# 9key_rev0_1a.net
KiCad netlist of a schematic drawn in EAGLE
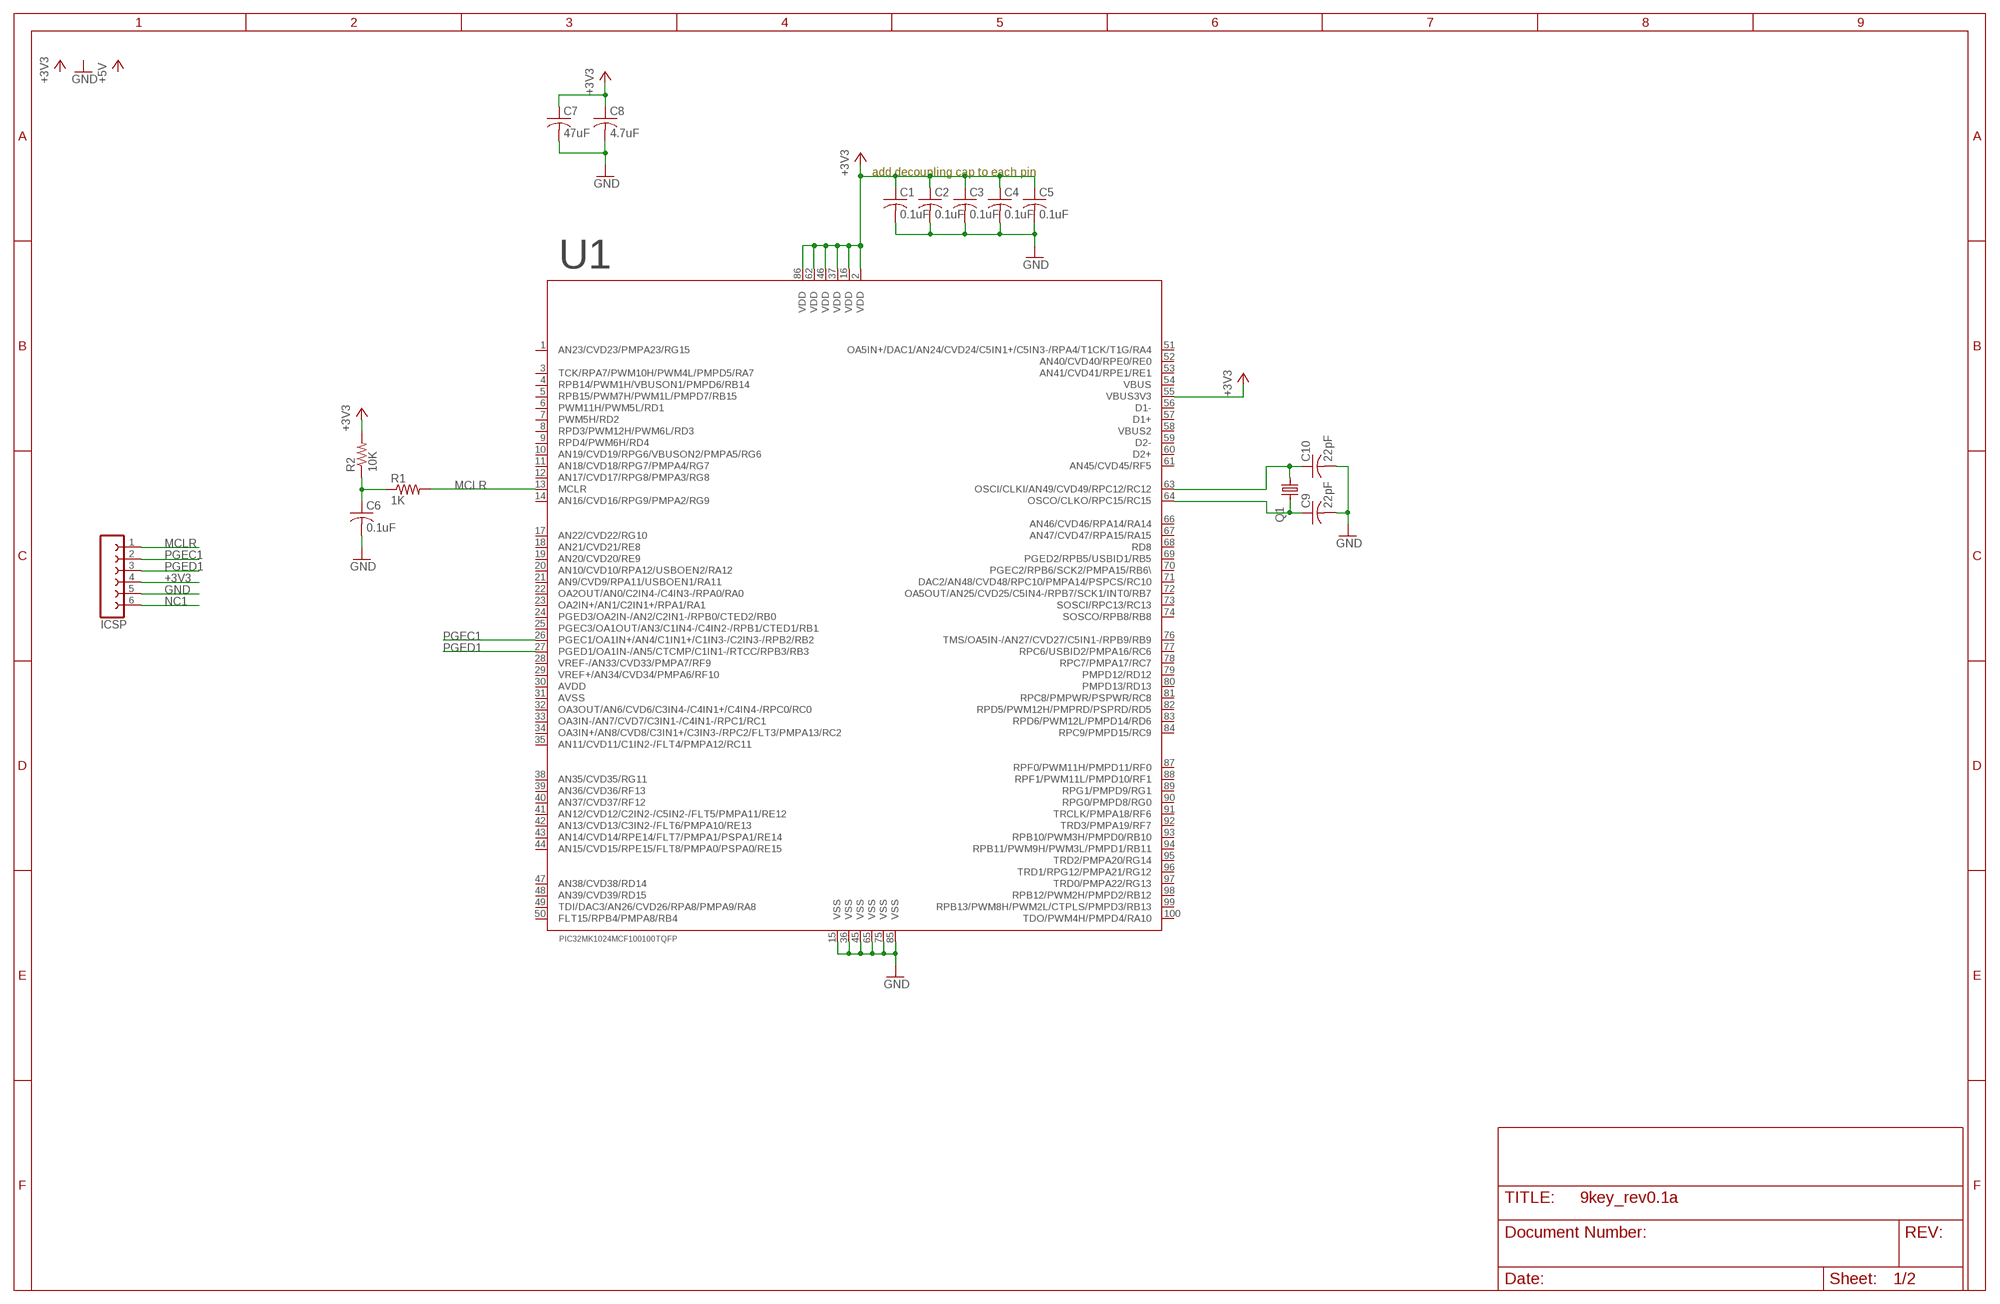
[diagram p0: schematic, sheet 1]
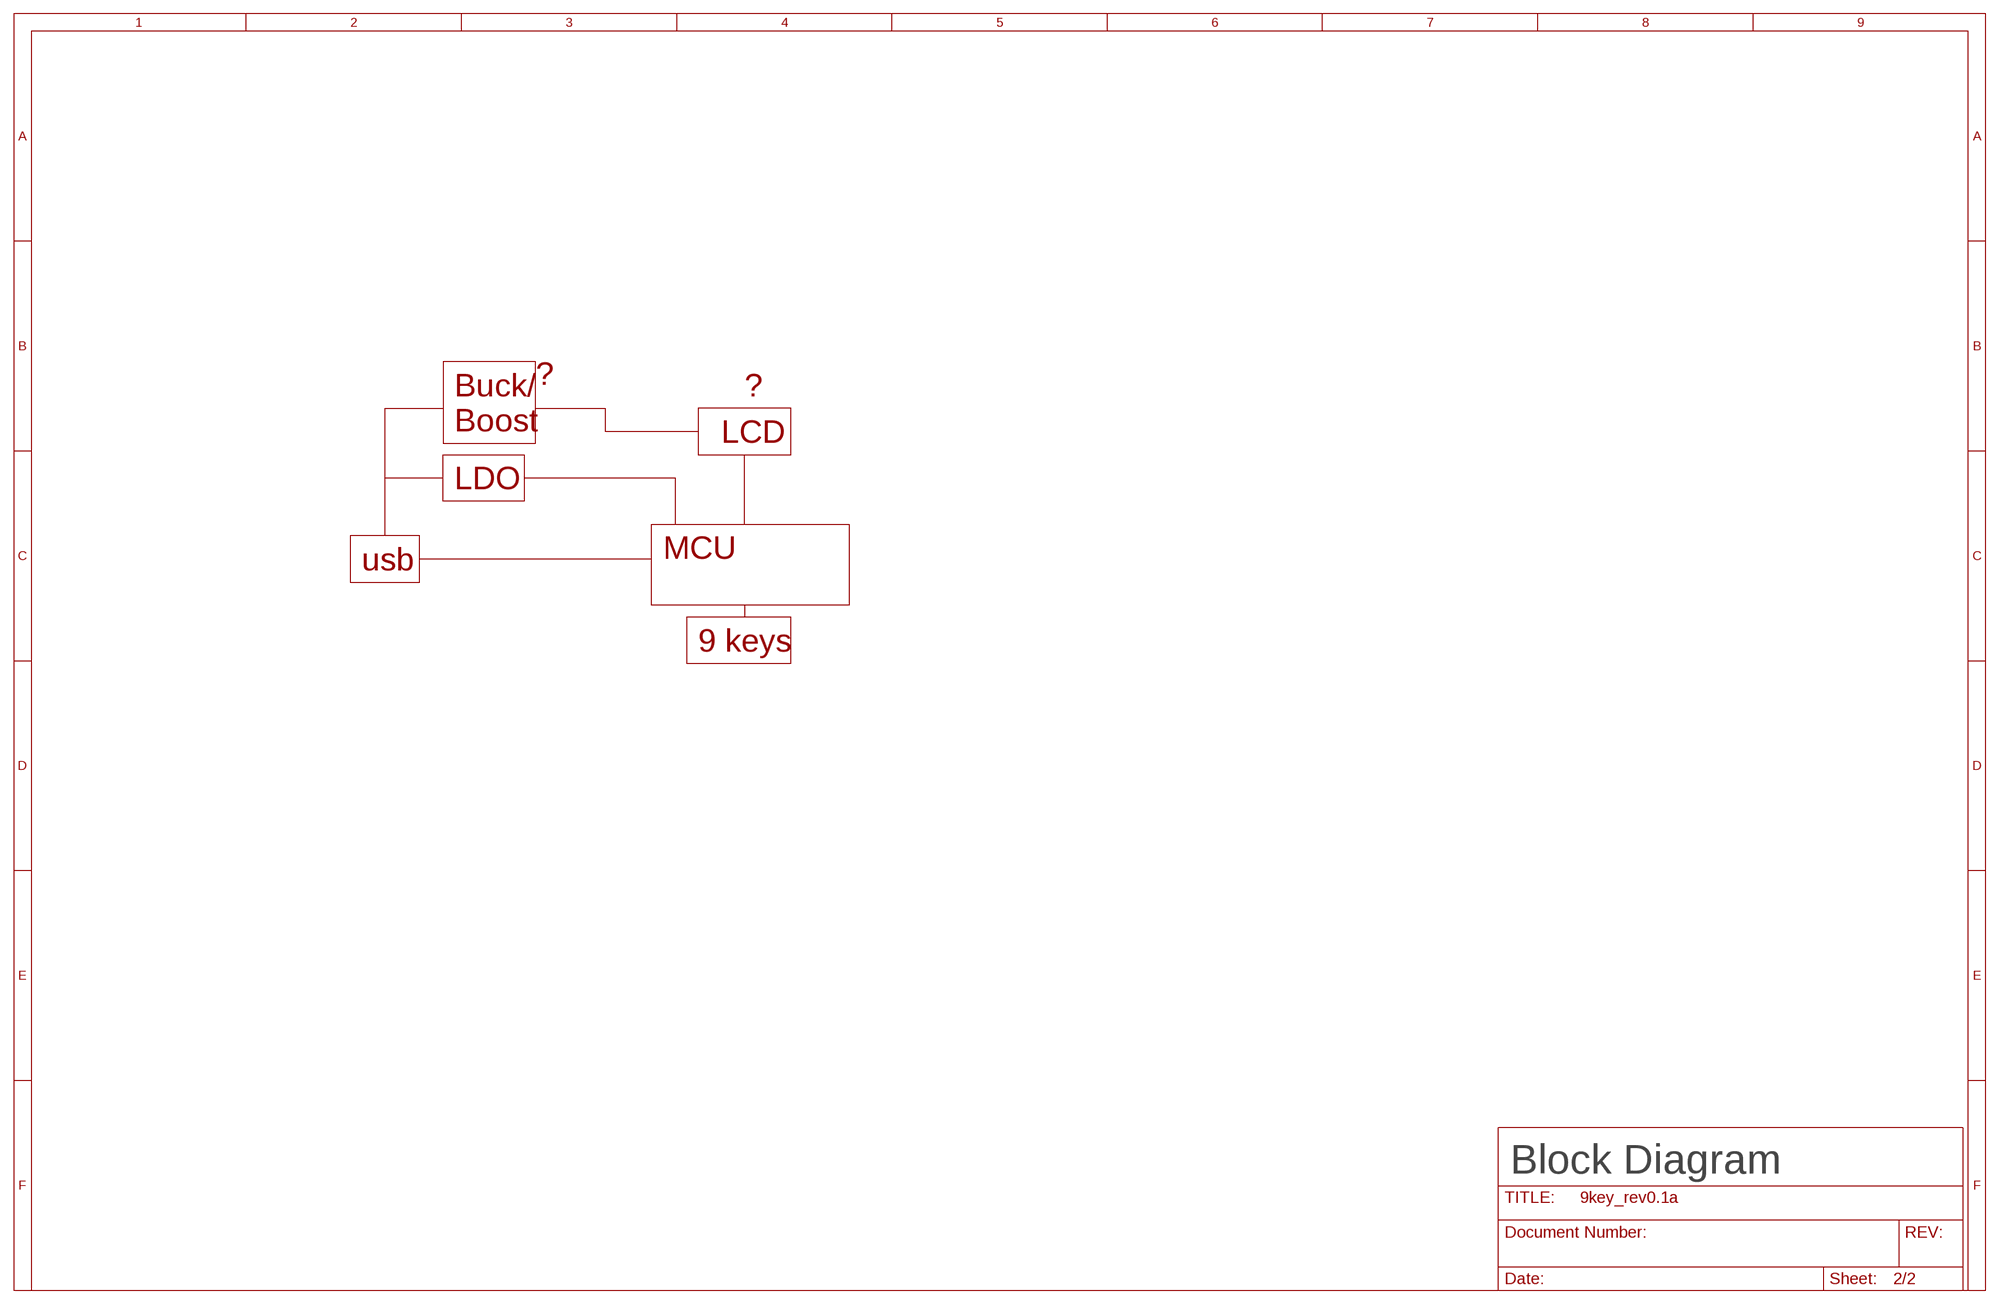
[diagram p1: schematic, sheet 2]

(export (version "E")
  (design (tool "Eeschema 10.0.6"))
  (components
    (comp (ref "C1")
      (value "0.1uF")
      (footprint "eagle-import:C0805")
      (libsource (lib "eagle-import") (part "C-USC0805"))
    )
    (comp (ref "C2")
      (value "0.1uF")
      (footprint "eagle-import:C0805")
      (libsource (lib "eagle-import") (part "C-USC0805"))
    )
    (comp (ref "C3")
      (value "0.1uF")
      (footprint "eagle-import:C0805")
      (libsource (lib "eagle-import") (part "C-USC0805"))
    )
    (comp (ref "C4")
      (value "0.1uF")
      (footprint "eagle-import:C0805")
      (libsource (lib "eagle-import") (part "C-USC0805"))
    )
    (comp (ref "C5")
      (value "0.1uF")
      (footprint "eagle-import:C0805")
      (libsource (lib "eagle-import") (part "C-USC0805"))
    )
    (comp (ref "C6")
      (value "0.1uF")
      (footprint "eagle-import:C0805")
      (libsource (lib "eagle-import") (part "C-USC0805"))
    )
    (comp (ref "C7")
      (value "47uF")
      (footprint "eagle-import:C0805")
      (libsource (lib "eagle-import") (part "C-USC0805"))
    )
    (comp (ref "C8")
      (value "4.7uF")
      (footprint "eagle-import:C0805")
      (libsource (lib "eagle-import") (part "C-USC0805"))
    )
    (comp (ref "C9")
      (value "22pF")
      (footprint "eagle-import:C0603")
      (libsource (lib "eagle-import") (part "C-USC0603"))
    )
    (comp (ref "C10")
      (value "22pF")
      (footprint "eagle-import:C0603")
      (libsource (lib "eagle-import") (part "C-USC0603"))
    )
    (comp (ref "ICSP")
      (value "FE06-1")
      (footprint "eagle-import:FE06")
      (libsource (lib "eagle-import") (part "FE06-1"))
    )
    (comp (ref "Q1")
      (value "KX-7")
      (footprint "eagle-import:3.2X2.5_KX-7")
      (libsource (lib "eagle-import") (part "KX-7"))
    )
    (comp (ref "R1")
      (value "1K")
      (footprint "eagle-import:R0805")
      (libsource (lib "eagle-import") (part "R-US_R0805"))
    )
    (comp (ref "R2")
      (value "10K")
      (footprint "eagle-import:R0805")
      (libsource (lib "eagle-import") (part "R-US_R0805"))
    )
    (comp (ref "U1")
      (value "PIC32MK1024MCF100100TQFP")
      (footprint "eagle-import:PIC32MK1024MCF100")
      (libsource (lib "eagle-import") (part "PIC32MK1024MCF100100TQFP"))
    )
  )
  (nets
    (net (code "1") (name "+3V3") (class "Default")
      (node (ref "C1") (pin "1") (pinfunction "1_1") (pintype "passive"))
      (node (ref "C2") (pin "1") (pinfunction "1_1") (pintype "passive"))
      (node (ref "C3") (pin "1") (pinfunction "1_1") (pintype "passive"))
      (node (ref "C4") (pin "1") (pinfunction "1_1") (pintype "passive"))
      (node (ref "C5") (pin "1") (pinfunction "1_1") (pintype "passive"))
      (node (ref "C7") (pin "1") (pinfunction "1_1") (pintype "passive"))
      (node (ref "C8") (pin "1") (pinfunction "1_1") (pintype "passive"))
      (node (ref "ICSP") (pin "4") (pinfunction "4_4") (pintype "passive"))
      (node (ref "R2") (pin "2") (pinfunction "2_2") (pintype "passive"))
      (node (ref "U1") (pin "16") (pinfunction "VDD_16") (pintype "bidirectional"))
      (node (ref "U1") (pin "2") (pinfunction "VDD_2") (pintype "bidirectional"))
      (node (ref "U1") (pin "37") (pinfunction "VDD_37") (pintype "bidirectional"))
      (node (ref "U1") (pin "46") (pinfunction "VDD_46") (pintype "bidirectional"))
      (node (ref "U1") (pin "55") (pinfunction "VBUS3V3_55") (pintype "bidirectional"))
      (node (ref "U1") (pin "62") (pinfunction "VDD_62") (pintype "bidirectional"))
      (node (ref "U1") (pin "86") (pinfunction "VDD_86") (pintype "bidirectional"))
    )
    (net (code "3") (name "GND") (class "Default")
      (node (ref "C1") (pin "2") (pinfunction "2_2") (pintype "passive"))
      (node (ref "C10") (pin "2") (pinfunction "2_2") (pintype "passive"))
      (node (ref "C2") (pin "2") (pinfunction "2_2") (pintype "passive"))
      (node (ref "C3") (pin "2") (pinfunction "2_2") (pintype "passive"))
      (node (ref "C4") (pin "2") (pinfunction "2_2") (pintype "passive"))
      (node (ref "C5") (pin "2") (pinfunction "2_2") (pintype "passive"))
      (node (ref "C6") (pin "2") (pinfunction "2_2") (pintype "passive"))
      (node (ref "C7") (pin "2") (pinfunction "2_2") (pintype "passive"))
      (node (ref "C8") (pin "2") (pinfunction "2_2") (pintype "passive"))
      (node (ref "C9") (pin "2") (pinfunction "2_2") (pintype "passive"))
      (node (ref "ICSP") (pin "5") (pinfunction "5_5") (pintype "passive"))
      (node (ref "U1") (pin "15") (pinfunction "VSS_15") (pintype "bidirectional"))
      (node (ref "U1") (pin "36") (pinfunction "VSS_36") (pintype "bidirectional"))
      (node (ref "U1") (pin "45") (pinfunction "VSS_45") (pintype "bidirectional"))
      (node (ref "U1") (pin "65") (pinfunction "VSS_65") (pintype "bidirectional"))
      (node (ref "U1") (pin "75") (pinfunction "VSS_75") (pintype "bidirectional"))
      (node (ref "U1") (pin "85") (pinfunction "VSS_85") (pintype "bidirectional"))
    )
    (net (code "4") (name "MCLR") (class "Default")
      (node (ref "ICSP") (pin "1") (pinfunction "1_1") (pintype "passive"))
      (node (ref "R1") (pin "2") (pinfunction "2_2") (pintype "passive"))
      (node (ref "U1") (pin "13") (pinfunction "MCLR_13") (pintype "bidirectional"))
    )
    (net (code "5") (name "NC1") (class "Default")
      (node (ref "ICSP") (pin "6") (pinfunction "6_6") (pintype "passive"))
    )
    (net (code "6") (name "Net-(C6-Pad1)") (class "Default")
      (node (ref "C6") (pin "1") (pinfunction "1_1") (pintype "passive"))
      (node (ref "R1") (pin "1") (pinfunction "1_1") (pintype "passive"))
      (node (ref "R2") (pin "1") (pinfunction "1_1") (pintype "passive"))
    )
    (net (code "7") (name "Net-(Q1-2)") (class "Default")
      (node (ref "C9") (pin "1") (pinfunction "1_1") (pintype "passive"))
      (node (ref "Q1") (pin "3") (pinfunction "2_3") (pintype "passive"))
      (node (ref "U1") (pin "64") (pinfunction "OSCO/CLKO/RPC15/RC15_64") (pintype "bidirectional"))
    )
    (net (code "8") (name "Net-(U1-OSCI{slash}CLKI{slash}AN49{slash}CVD49{slash}RPC12{slash}RC12)") (class "Default")
      (node (ref "C10") (pin "1") (pinfunction "1_1") (pintype "passive"))
      (node (ref "Q1") (pin "1") (pinfunction "1_1") (pintype "passive"))
      (node (ref "U1") (pin "63") (pinfunction "OSCI/CLKI/AN49/CVD49/RPC12/RC12_63") (pintype "bidirectional"))
    )
    (net (code "9") (name "PGEC1") (class "Default")
      (node (ref "ICSP") (pin "2") (pinfunction "2_2") (pintype "passive"))
      (node (ref "U1") (pin "26") (pinfunction "PGEC1/OA1IN+/AN4/C1IN1+/C1IN3-/C2IN3-/RPB2/RB2_26") (pintype "bidirectional"))
    )
    (net (code "10") (name "PGED1") (class "Default")
      (node (ref "ICSP") (pin "3") (pinfunction "3_3") (pintype "passive"))
      (node (ref "U1") (pin "27") (pinfunction "PGED1/OA1IN-/AN5/CTCMP/C1IN1-/RTCC/RPB3/RB3_27") (pintype "bidirectional"))
    )
    (net (code "11") (name "unconnected-(U1-AN9{slash}CVD9{slash}RPA11{slash}USBOEN1{slash}RA11-Pad21)") (class "Default")
      (node (ref "U1") (pin "21") (pinfunction "AN9/CVD9/RPA11/USBOEN1/RA11_21") (pintype "bidirectional"))
    )
    (net (code "12") (name "unconnected-(U1-AN10{slash}CVD10{slash}RPA12{slash}USBOEN2{slash}RA12-Pad20)") (class "Default")
      (node (ref "U1") (pin "20") (pinfunction "AN10/CVD10/RPA12/USBOEN2/RA12_20") (pintype "bidirectional"))
    )
    (net (code "13") (name "unconnected-(U1-AN11{slash}CVD11{slash}C1IN2-{slash}FLT4{slash}PMPA12{slash}RC11-Pad35)") (class "Default")
      (node (ref "U1") (pin "35") (pinfunction "AN11/CVD11/C1IN2-/FLT4/PMPA12/RC11_35") (pintype "bidirectional"))
    )
    (net (code "14") (name "unconnected-(U1-AN12{slash}CVD12{slash}C2IN2-{slash}C5IN2-{slash}FLT5{slash}PMPA11{slash}RE12-Pad41)") (class "Default")
      (node (ref "U1") (pin "41") (pinfunction "AN12/CVD12/C2IN2-/C5IN2-/FLT5/PMPA11/RE12_41") (pintype "bidirectional"))
    )
    (net (code "15") (name "unconnected-(U1-AN13{slash}CVD13{slash}C3IN2-{slash}FLT6{slash}PMPA10{slash}RE13-Pad42)") (class "Default")
      (node (ref "U1") (pin "42") (pinfunction "AN13/CVD13/C3IN2-/FLT6/PMPA10/RE13_42") (pintype "bidirectional"))
    )
    (net (code "16") (name "unconnected-(U1-AN14{slash}CVD14{slash}RPE14{slash}FLT7{slash}PMPA1{slash}PSPA1{slash}RE14-Pad43)") (class "Default")
      (node (ref "U1") (pin "43") (pinfunction "AN14/CVD14/RPE14/FLT7/PMPA1/PSPA1/RE14_43") (pintype "bidirectional"))
    )
    (net (code "17") (name "unconnected-(U1-AN15{slash}CVD15{slash}RPE15{slash}FLT8{slash}PMPA0{slash}PSPA0{slash}RE15-Pad44)") (class "Default")
      (node (ref "U1") (pin "44") (pinfunction "AN15/CVD15/RPE15/FLT8/PMPA0/PSPA0/RE15_44") (pintype "bidirectional"))
    )
    (net (code "18") (name "unconnected-(U1-AN16{slash}CVD16{slash}RPG9{slash}PMPA2{slash}RG9-Pad14)") (class "Default")
      (node (ref "U1") (pin "14") (pinfunction "AN16/CVD16/RPG9/PMPA2/RG9_14") (pintype "bidirectional"))
    )
    (net (code "19") (name "unconnected-(U1-AN17{slash}CVD17{slash}RPG8{slash}PMPA3{slash}RG8-Pad12)") (class "Default")
      (node (ref "U1") (pin "12") (pinfunction "AN17/CVD17/RPG8/PMPA3/RG8_12") (pintype "bidirectional"))
    )
    (net (code "20") (name "unconnected-(U1-AN18{slash}CVD18{slash}RPG7{slash}PMPA4{slash}RG7-Pad11)") (class "Default")
      (node (ref "U1") (pin "11") (pinfunction "AN18/CVD18/RPG7/PMPA4/RG7_11") (pintype "bidirectional"))
    )
    (net (code "21") (name "unconnected-(U1-AN19{slash}CVD19{slash}RPG6{slash}VBUSON2{slash}PMPA5{slash}RG6-Pad10)") (class "Default")
      (node (ref "U1") (pin "10") (pinfunction "AN19/CVD19/RPG6/VBUSON2/PMPA5/RG6_10") (pintype "bidirectional"))
    )
    (net (code "22") (name "unconnected-(U1-AN20{slash}CVD20{slash}RE9-Pad19)") (class "Default")
      (node (ref "U1") (pin "19") (pinfunction "AN20/CVD20/RE9_19") (pintype "bidirectional"))
    )
    (net (code "23") (name "unconnected-(U1-AN21{slash}CVD21{slash}RE8-Pad18)") (class "Default")
      (node (ref "U1") (pin "18") (pinfunction "AN21/CVD21/RE8_18") (pintype "bidirectional"))
    )
    (net (code "24") (name "unconnected-(U1-AN22{slash}CVD22{slash}RG10-Pad17)") (class "Default")
      (node (ref "U1") (pin "17") (pinfunction "AN22/CVD22/RG10_17") (pintype "bidirectional"))
    )
    (net (code "25") (name "unconnected-(U1-AN23{slash}CVD23{slash}PMPA23{slash}RG15-Pad1)") (class "Default")
      (node (ref "U1") (pin "1") (pinfunction "AN23/CVD23/PMPA23/RG15_1") (pintype "bidirectional"))
    )
    (net (code "26") (name "unconnected-(U1-AN35{slash}CVD35{slash}RG11-Pad38)") (class "Default")
      (node (ref "U1") (pin "38") (pinfunction "AN35/CVD35/RG11_38") (pintype "bidirectional"))
    )
    (net (code "27") (name "unconnected-(U1-AN36{slash}CVD36{slash}RF13-Pad39)") (class "Default")
      (node (ref "U1") (pin "39") (pinfunction "AN36/CVD36/RF13_39") (pintype "bidirectional"))
    )
    (net (code "28") (name "unconnected-(U1-AN37{slash}CVD37{slash}RF12-Pad40)") (class "Default")
      (node (ref "U1") (pin "40") (pinfunction "AN37/CVD37/RF12_40") (pintype "bidirectional"))
    )
    (net (code "29") (name "unconnected-(U1-AN38{slash}CVD38{slash}RD14-Pad47)") (class "Default")
      (node (ref "U1") (pin "47") (pinfunction "AN38/CVD38/RD14_47") (pintype "bidirectional"))
    )
    (net (code "30") (name "unconnected-(U1-AN39{slash}CVD39{slash}RD15-Pad48)") (class "Default")
      (node (ref "U1") (pin "48") (pinfunction "AN39/CVD39/RD15_48") (pintype "bidirectional"))
    )
    (net (code "31") (name "unconnected-(U1-AN40{slash}CVD40{slash}RPE0{slash}RE0-Pad52)") (class "Default")
      (node (ref "U1") (pin "52") (pinfunction "AN40/CVD40/RPE0/RE0_52") (pintype "bidirectional"))
    )
    (net (code "32") (name "unconnected-(U1-AN41{slash}CVD41{slash}RPE1{slash}RE1-Pad53)") (class "Default")
      (node (ref "U1") (pin "53") (pinfunction "AN41/CVD41/RPE1/RE1_53") (pintype "bidirectional"))
    )
    (net (code "33") (name "unconnected-(U1-AN45{slash}CVD45{slash}RF5-Pad61)") (class "Default")
      (node (ref "U1") (pin "61") (pinfunction "AN45/CVD45/RF5_61") (pintype "bidirectional"))
    )
    (net (code "34") (name "unconnected-(U1-AN46{slash}CVD46{slash}RPA14{slash}RA14-Pad66)") (class "Default")
      (node (ref "U1") (pin "66") (pinfunction "AN46/CVD46/RPA14/RA14_66") (pintype "bidirectional"))
    )
    (net (code "35") (name "unconnected-(U1-AN47{slash}CVD47{slash}RPA15{slash}RA15-Pad67)") (class "Default")
      (node (ref "U1") (pin "67") (pinfunction "AN47/CVD47/RPA15/RA15_67") (pintype "bidirectional"))
    )
    (net (code "36") (name "unconnected-(U1-AVDD-Pad30)") (class "Default")
      (node (ref "U1") (pin "30") (pinfunction "AVDD_30") (pintype "bidirectional"))
    )
    (net (code "37") (name "unconnected-(U1-AVSS-Pad31)") (class "Default")
      (node (ref "U1") (pin "31") (pinfunction "AVSS_31") (pintype "bidirectional"))
    )
    (net (code "38") (name "unconnected-(U1-D1+-Pad57)") (class "Default")
      (node (ref "U1") (pin "57") (pinfunction "D1+_57") (pintype "bidirectional"))
    )
    (net (code "39") (name "unconnected-(U1-D1--Pad56)") (class "Default")
      (node (ref "U1") (pin "56") (pinfunction "D1-_56") (pintype "bidirectional"))
    )
    (net (code "40") (name "unconnected-(U1-D2+-Pad60)") (class "Default")
      (node (ref "U1") (pin "60") (pinfunction "D2+_60") (pintype "bidirectional"))
    )
    (net (code "41") (name "unconnected-(U1-D2--Pad59)") (class "Default")
      (node (ref "U1") (pin "59") (pinfunction "D2-_59") (pintype "bidirectional"))
    )
    (net (code "42") (name "unconnected-(U1-DAC2{slash}AN48{slash}CVD48{slash}RPC10{slash}PMPA14{slash}PSPCS{slash}RC10-Pad71)") (class "Default")
      (node (ref "U1") (pin "71") (pinfunction "DAC2/AN48/CVD48/RPC10/PMPA14/PSPCS/RC10_71") (pintype "bidirectional"))
    )
    (net (code "43") (name "unconnected-(U1-FLT15{slash}RPB4{slash}PMPA8{slash}RB4-Pad50)") (class "Default")
      (node (ref "U1") (pin "50") (pinfunction "FLT15/RPB4/PMPA8/RB4_50") (pintype "bidirectional"))
    )
    (net (code "44") (name "unconnected-(U1-OA2IN+{slash}AN1{slash}C2IN1+{slash}RPA1{slash}RA1-Pad23)") (class "Default")
      (node (ref "U1") (pin "23") (pinfunction "OA2IN+/AN1/C2IN1+/RPA1/RA1_23") (pintype "bidirectional"))
    )
    (net (code "45") (name "unconnected-(U1-OA2OUT{slash}AN0{slash}C2IN4-{slash}C4IN3-{slash}RPA0{slash}RA0-Pad22)") (class "Default")
      (node (ref "U1") (pin "22") (pinfunction "OA2OUT/AN0/C2IN4-/C4IN3-/RPA0/RA0_22") (pintype "bidirectional"))
    )
    (net (code "46") (name "unconnected-(U1-OA3IN+{slash}AN8{slash}CVD8{slash}C3IN1+{slash}C3IN3-{slash}RPC2{slash}FLT3{slash}PMPA13{slash}RC2-Pad34)") (class "Default")
      (node (ref "U1") (pin "34") (pinfunction "OA3IN+/AN8/CVD8/C3IN1+/C3IN3-/RPC2/FLT3/PMPA13/RC2_34") (pintype "bidirectional"))
    )
    (net (code "47") (name "unconnected-(U1-OA3IN-{slash}AN7{slash}CVD7{slash}C3IN1-{slash}C4IN1-{slash}RPC1{slash}RC1-Pad33)") (class "Default")
      (node (ref "U1") (pin "33") (pinfunction "OA3IN-/AN7/CVD7/C3IN1-/C4IN1-/RPC1/RC1_33") (pintype "bidirectional"))
    )
    (net (code "48") (name "unconnected-(U1-OA3OUT{slash}AN6{slash}CVD6{slash}C3IN4-{slash}C4IN1+{slash}C4IN4-{slash}RPC0{slash}RC0-Pad32)") (class "Default")
      (node (ref "U1") (pin "32") (pinfunction "OA3OUT/AN6/CVD6/C3IN4-/C4IN1+/C4IN4-/RPC0/RC0_32") (pintype "bidirectional"))
    )
    (net (code "49") (name "unconnected-(U1-OA5IN+{slash}DAC1{slash}AN24{slash}CVD24{slash}C5IN1+{slash}C5IN3-{slash}RPA4{slash}T1CK{slash}T1G{slash}RA4-Pad51)") (class "Default")
      (node (ref "U1") (pin "51") (pinfunction "OA5IN+/DAC1/AN24/CVD24/C5IN1+/C5IN3-/RPA4/T1CK/T1G/RA4_51") (pintype "bidirectional"))
    )
    (net (code "50") (name "unconnected-(U1-OA5OUT{slash}AN25{slash}CVD25{slash}C5IN4-{slash}RPB7{slash}SCK1{slash}INT0{slash}RB7-Pad72)") (class "Default")
      (node (ref "U1") (pin "72") (pinfunction "OA5OUT/AN25/CVD25/C5IN4-/RPB7/SCK1/INT0/RB7_72") (pintype "bidirectional"))
    )
    (net (code "51") (name "unconnected-(U1-PGEC2{slash}RPB6{slash}SCK2{slash}PMPA15{slash}RB6\\-Pad70)") (class "Default")
      (node (ref "U1") (pin "70") (pinfunction "PGEC2/RPB6/SCK2/PMPA15/RB6\\_70") (pintype "bidirectional"))
    )
    (net (code "52") (name "unconnected-(U1-PGEC3{slash}OA1OUT{slash}AN3{slash}C1IN4-{slash}C4IN2-{slash}RPB1{slash}CTED1{slash}RB1-Pad25)") (class "Default")
      (node (ref "U1") (pin "25") (pinfunction "PGEC3/OA1OUT/AN3/C1IN4-/C4IN2-/RPB1/CTED1/RB1_25") (pintype "bidirectional"))
    )
    (net (code "53") (name "unconnected-(U1-PGED2{slash}RPB5{slash}USBID1{slash}RB5-Pad69)") (class "Default")
      (node (ref "U1") (pin "69") (pinfunction "PGED2/RPB5/USBID1/RB5_69") (pintype "bidirectional"))
    )
    (net (code "54") (name "unconnected-(U1-PGED3{slash}OA2IN-{slash}AN2{slash}C2IN1-{slash}RPB0{slash}CTED2{slash}RB0-Pad24)") (class "Default")
      (node (ref "U1") (pin "24") (pinfunction "PGED3/OA2IN-/AN2/C2IN1-/RPB0/CTED2/RB0_24") (pintype "bidirectional"))
    )
    (net (code "55") (name "unconnected-(U1-PMPD12{slash}RD12-Pad79)") (class "Default")
      (node (ref "U1") (pin "79") (pinfunction "PMPD12/RD12_79") (pintype "bidirectional"))
    )
    (net (code "56") (name "unconnected-(U1-PMPD13{slash}RD13-Pad80)") (class "Default")
      (node (ref "U1") (pin "80") (pinfunction "PMPD13/RD13_80") (pintype "bidirectional"))
    )
    (net (code "57") (name "unconnected-(U1-PWM5H{slash}RD2-Pad7)") (class "Default")
      (node (ref "U1") (pin "7") (pinfunction "PWM5H/RD2_7") (pintype "bidirectional"))
    )
    (net (code "58") (name "unconnected-(U1-PWM11H{slash}PWM5L{slash}RD1-Pad6)") (class "Default")
      (node (ref "U1") (pin "6") (pinfunction "PWM11H/PWM5L/RD1_6") (pintype "bidirectional"))
    )
    (net (code "59") (name "unconnected-(U1-RD8-Pad68)") (class "Default")
      (node (ref "U1") (pin "68") (pinfunction "RD8_68") (pintype "bidirectional"))
    )
    (net (code "60") (name "unconnected-(U1-RPB10{slash}PWM3H{slash}PMPD0{slash}RB10-Pad93)") (class "Default")
      (node (ref "U1") (pin "93") (pinfunction "RPB10/PWM3H/PMPD0/RB10_93") (pintype "bidirectional"))
    )
    (net (code "61") (name "unconnected-(U1-RPB11{slash}PWM9H{slash}PWM3L{slash}PMPD1{slash}RB11-Pad94)") (class "Default")
      (node (ref "U1") (pin "94") (pinfunction "RPB11/PWM9H/PWM3L/PMPD1/RB11_94") (pintype "bidirectional"))
    )
    (net (code "62") (name "unconnected-(U1-RPB12{slash}PWM2H{slash}PMPD2{slash}RB12-Pad98)") (class "Default")
      (node (ref "U1") (pin "98") (pinfunction "RPB12/PWM2H/PMPD2/RB12_98") (pintype "bidirectional"))
    )
    (net (code "63") (name "unconnected-(U1-RPB13{slash}PWM8H{slash}PWM2L{slash}CTPLS{slash}PMPD3{slash}RB13-Pad99)") (class "Default")
      (node (ref "U1") (pin "99") (pinfunction "RPB13/PWM8H/PWM2L/CTPLS/PMPD3/RB13_99") (pintype "bidirectional"))
    )
    (net (code "64") (name "unconnected-(U1-RPB14{slash}PWM1H{slash}VBUSON1{slash}PMPD6{slash}RB14-Pad4)") (class "Default")
      (node (ref "U1") (pin "4") (pinfunction "RPB14/PWM1H/VBUSON1/PMPD6/RB14_4") (pintype "bidirectional"))
    )
    (net (code "65") (name "unconnected-(U1-RPB15{slash}PWM7H{slash}PWM1L{slash}PMPD7{slash}RB15-Pad5)") (class "Default")
      (node (ref "U1") (pin "5") (pinfunction "RPB15/PWM7H/PWM1L/PMPD7/RB15_5") (pintype "bidirectional"))
    )
    (net (code "66") (name "unconnected-(U1-RPC6{slash}USBID2{slash}PMPA16{slash}RC6-Pad77)") (class "Default")
      (node (ref "U1") (pin "77") (pinfunction "RPC6/USBID2/PMPA16/RC6_77") (pintype "bidirectional"))
    )
    (net (code "67") (name "unconnected-(U1-RPC7{slash}PMPA17{slash}RC7-Pad78)") (class "Default")
      (node (ref "U1") (pin "78") (pinfunction "RPC7/PMPA17/RC7_78") (pintype "bidirectional"))
    )
    (net (code "68") (name "unconnected-(U1-RPC8{slash}PMPWR{slash}PSPWR{slash}RC8-Pad81)") (class "Default")
      (node (ref "U1") (pin "81") (pinfunction "RPC8/PMPWR/PSPWR/RC8_81") (pintype "bidirectional"))
    )
    (net (code "69") (name "unconnected-(U1-RPC9{slash}PMPD15{slash}RC9-Pad84)") (class "Default")
      (node (ref "U1") (pin "84") (pinfunction "RPC9/PMPD15/RC9_84") (pintype "bidirectional"))
    )
    (net (code "70") (name "unconnected-(U1-RPD3{slash}PWM12H{slash}PWM6L{slash}RD3-Pad8)") (class "Default")
      (node (ref "U1") (pin "8") (pinfunction "RPD3/PWM12H/PWM6L/RD3_8") (pintype "bidirectional"))
    )
    (net (code "71") (name "unconnected-(U1-RPD4{slash}PWM6H{slash}RD4-Pad9)") (class "Default")
      (node (ref "U1") (pin "9") (pinfunction "RPD4/PWM6H/RD4_9") (pintype "bidirectional"))
    )
    (net (code "72") (name "unconnected-(U1-RPD5{slash}PWM12H{slash}PMPRD{slash}PSPRD{slash}RD5-Pad82)") (class "Default")
      (node (ref "U1") (pin "82") (pinfunction "RPD5/PWM12H/PMPRD/PSPRD/RD5_82") (pintype "bidirectional"))
    )
    (net (code "73") (name "unconnected-(U1-RPD6{slash}PWM12L{slash}PMPD14{slash}RD6-Pad83)") (class "Default")
      (node (ref "U1") (pin "83") (pinfunction "RPD6/PWM12L/PMPD14/RD6_83") (pintype "bidirectional"))
    )
    (net (code "74") (name "unconnected-(U1-RPF0{slash}PWM11H{slash}PMPD11{slash}RF0-Pad87)") (class "Default")
      (node (ref "U1") (pin "87") (pinfunction "RPF0/PWM11H/PMPD11/RF0_87") (pintype "bidirectional"))
    )
    (net (code "75") (name "unconnected-(U1-RPF1{slash}PWM11L{slash}PMPD10{slash}RF1-Pad88)") (class "Default")
      (node (ref "U1") (pin "88") (pinfunction "RPF1/PWM11L/PMPD10/RF1_88") (pintype "bidirectional"))
    )
    (net (code "76") (name "unconnected-(U1-RPG0{slash}PMPD8{slash}RG0-Pad90)") (class "Default")
      (node (ref "U1") (pin "90") (pinfunction "RPG0/PMPD8/RG0_90") (pintype "bidirectional"))
    )
    (net (code "77") (name "unconnected-(U1-RPG1{slash}PMPD9{slash}RG1-Pad89)") (class "Default")
      (node (ref "U1") (pin "89") (pinfunction "RPG1/PMPD9/RG1_89") (pintype "bidirectional"))
    )
    (net (code "78") (name "unconnected-(U1-SOSCI{slash}RPC13{slash}RC13-Pad73)") (class "Default")
      (node (ref "U1") (pin "73") (pinfunction "SOSCI/RPC13/RC13_73") (pintype "bidirectional"))
    )
    (net (code "79") (name "unconnected-(U1-SOSCO{slash}RPB8{slash}RB8-Pad74)") (class "Default")
      (node (ref "U1") (pin "74") (pinfunction "SOSCO/RPB8/RB8_74") (pintype "bidirectional"))
    )
    (net (code "80") (name "unconnected-(U1-TCK{slash}RPA7{slash}PWM10H{slash}PWM4L{slash}PMPD5{slash}RA7-Pad3)") (class "Default")
      (node (ref "U1") (pin "3") (pinfunction "TCK/RPA7/PWM10H/PWM4L/PMPD5/RA7_3") (pintype "bidirectional"))
    )
    (net (code "81") (name "unconnected-(U1-TDI{slash}DAC3{slash}AN26{slash}CVD26{slash}RPA8{slash}PMPA9{slash}RA8-Pad49)") (class "Default")
      (node (ref "U1") (pin "49") (pinfunction "TDI/DAC3/AN26/CVD26/RPA8/PMPA9/RA8_49") (pintype "bidirectional"))
    )
    (net (code "82") (name "unconnected-(U1-TDO{slash}PWM4H{slash}PMPD4{slash}RA10-Pad100)") (class "Default")
      (node (ref "U1") (pin "100") (pinfunction "TDO/PWM4H/PMPD4/RA10_100") (pintype "bidirectional"))
    )
    (net (code "83") (name "unconnected-(U1-TMS{slash}OA5IN-{slash}AN27{slash}CVD27{slash}C5IN1-{slash}RPB9{slash}RB9-Pad76)") (class "Default")
      (node (ref "U1") (pin "76") (pinfunction "TMS/OA5IN-/AN27/CVD27/C5IN1-/RPB9/RB9_76") (pintype "bidirectional"))
    )
    (net (code "84") (name "unconnected-(U1-TRCLK{slash}PMPA18{slash}RF6-Pad91)") (class "Default")
      (node (ref "U1") (pin "91") (pinfunction "TRCLK/PMPA18/RF6_91") (pintype "bidirectional"))
    )
    (net (code "85") (name "unconnected-(U1-TRD0{slash}PMPA22{slash}RG13-Pad97)") (class "Default")
      (node (ref "U1") (pin "97") (pinfunction "TRD0/PMPA22/RG13_97") (pintype "bidirectional"))
    )
    (net (code "86") (name "unconnected-(U1-TRD1{slash}RPG12{slash}PMPA21{slash}RG12-Pad96)") (class "Default")
      (node (ref "U1") (pin "96") (pinfunction "TRD1/RPG12/PMPA21/RG12_96") (pintype "bidirectional"))
    )
    (net (code "87") (name "unconnected-(U1-TRD2{slash}PMPA20{slash}RG14-Pad95)") (class "Default")
      (node (ref "U1") (pin "95") (pinfunction "TRD2/PMPA20/RG14_95") (pintype "bidirectional"))
    )
    (net (code "88") (name "unconnected-(U1-TRD3{slash}PMPA19{slash}RF7-Pad92)") (class "Default")
      (node (ref "U1") (pin "92") (pinfunction "TRD3/PMPA19/RF7_92") (pintype "bidirectional"))
    )
    (net (code "89") (name "unconnected-(U1-VBUS-Pad54)") (class "Default")
      (node (ref "U1") (pin "54") (pinfunction "VBUS_54") (pintype "bidirectional"))
    )
    (net (code "90") (name "unconnected-(U1-VBUS2-Pad58)") (class "Default")
      (node (ref "U1") (pin "58") (pinfunction "VBUS2_58") (pintype "bidirectional"))
    )
    (net (code "91") (name "unconnected-(U1-VREF+{slash}AN34{slash}CVD34{slash}PMPA6{slash}RF10-Pad29)") (class "Default")
      (node (ref "U1") (pin "29") (pinfunction "VREF+/AN34/CVD34/PMPA6/RF10_29") (pintype "bidirectional"))
    )
    (net (code "92") (name "unconnected-(U1-VREF-{slash}AN33{slash}CVD33{slash}PMPA7{slash}RF9-Pad28)") (class "Default")
      (node (ref "U1") (pin "28") (pinfunction "VREF-/AN33/CVD33/PMPA7/RF9_28") (pintype "bidirectional"))
    )
  )
)
